# POWER.net
KiCad netlist of a schematic drawn in Altium Designer
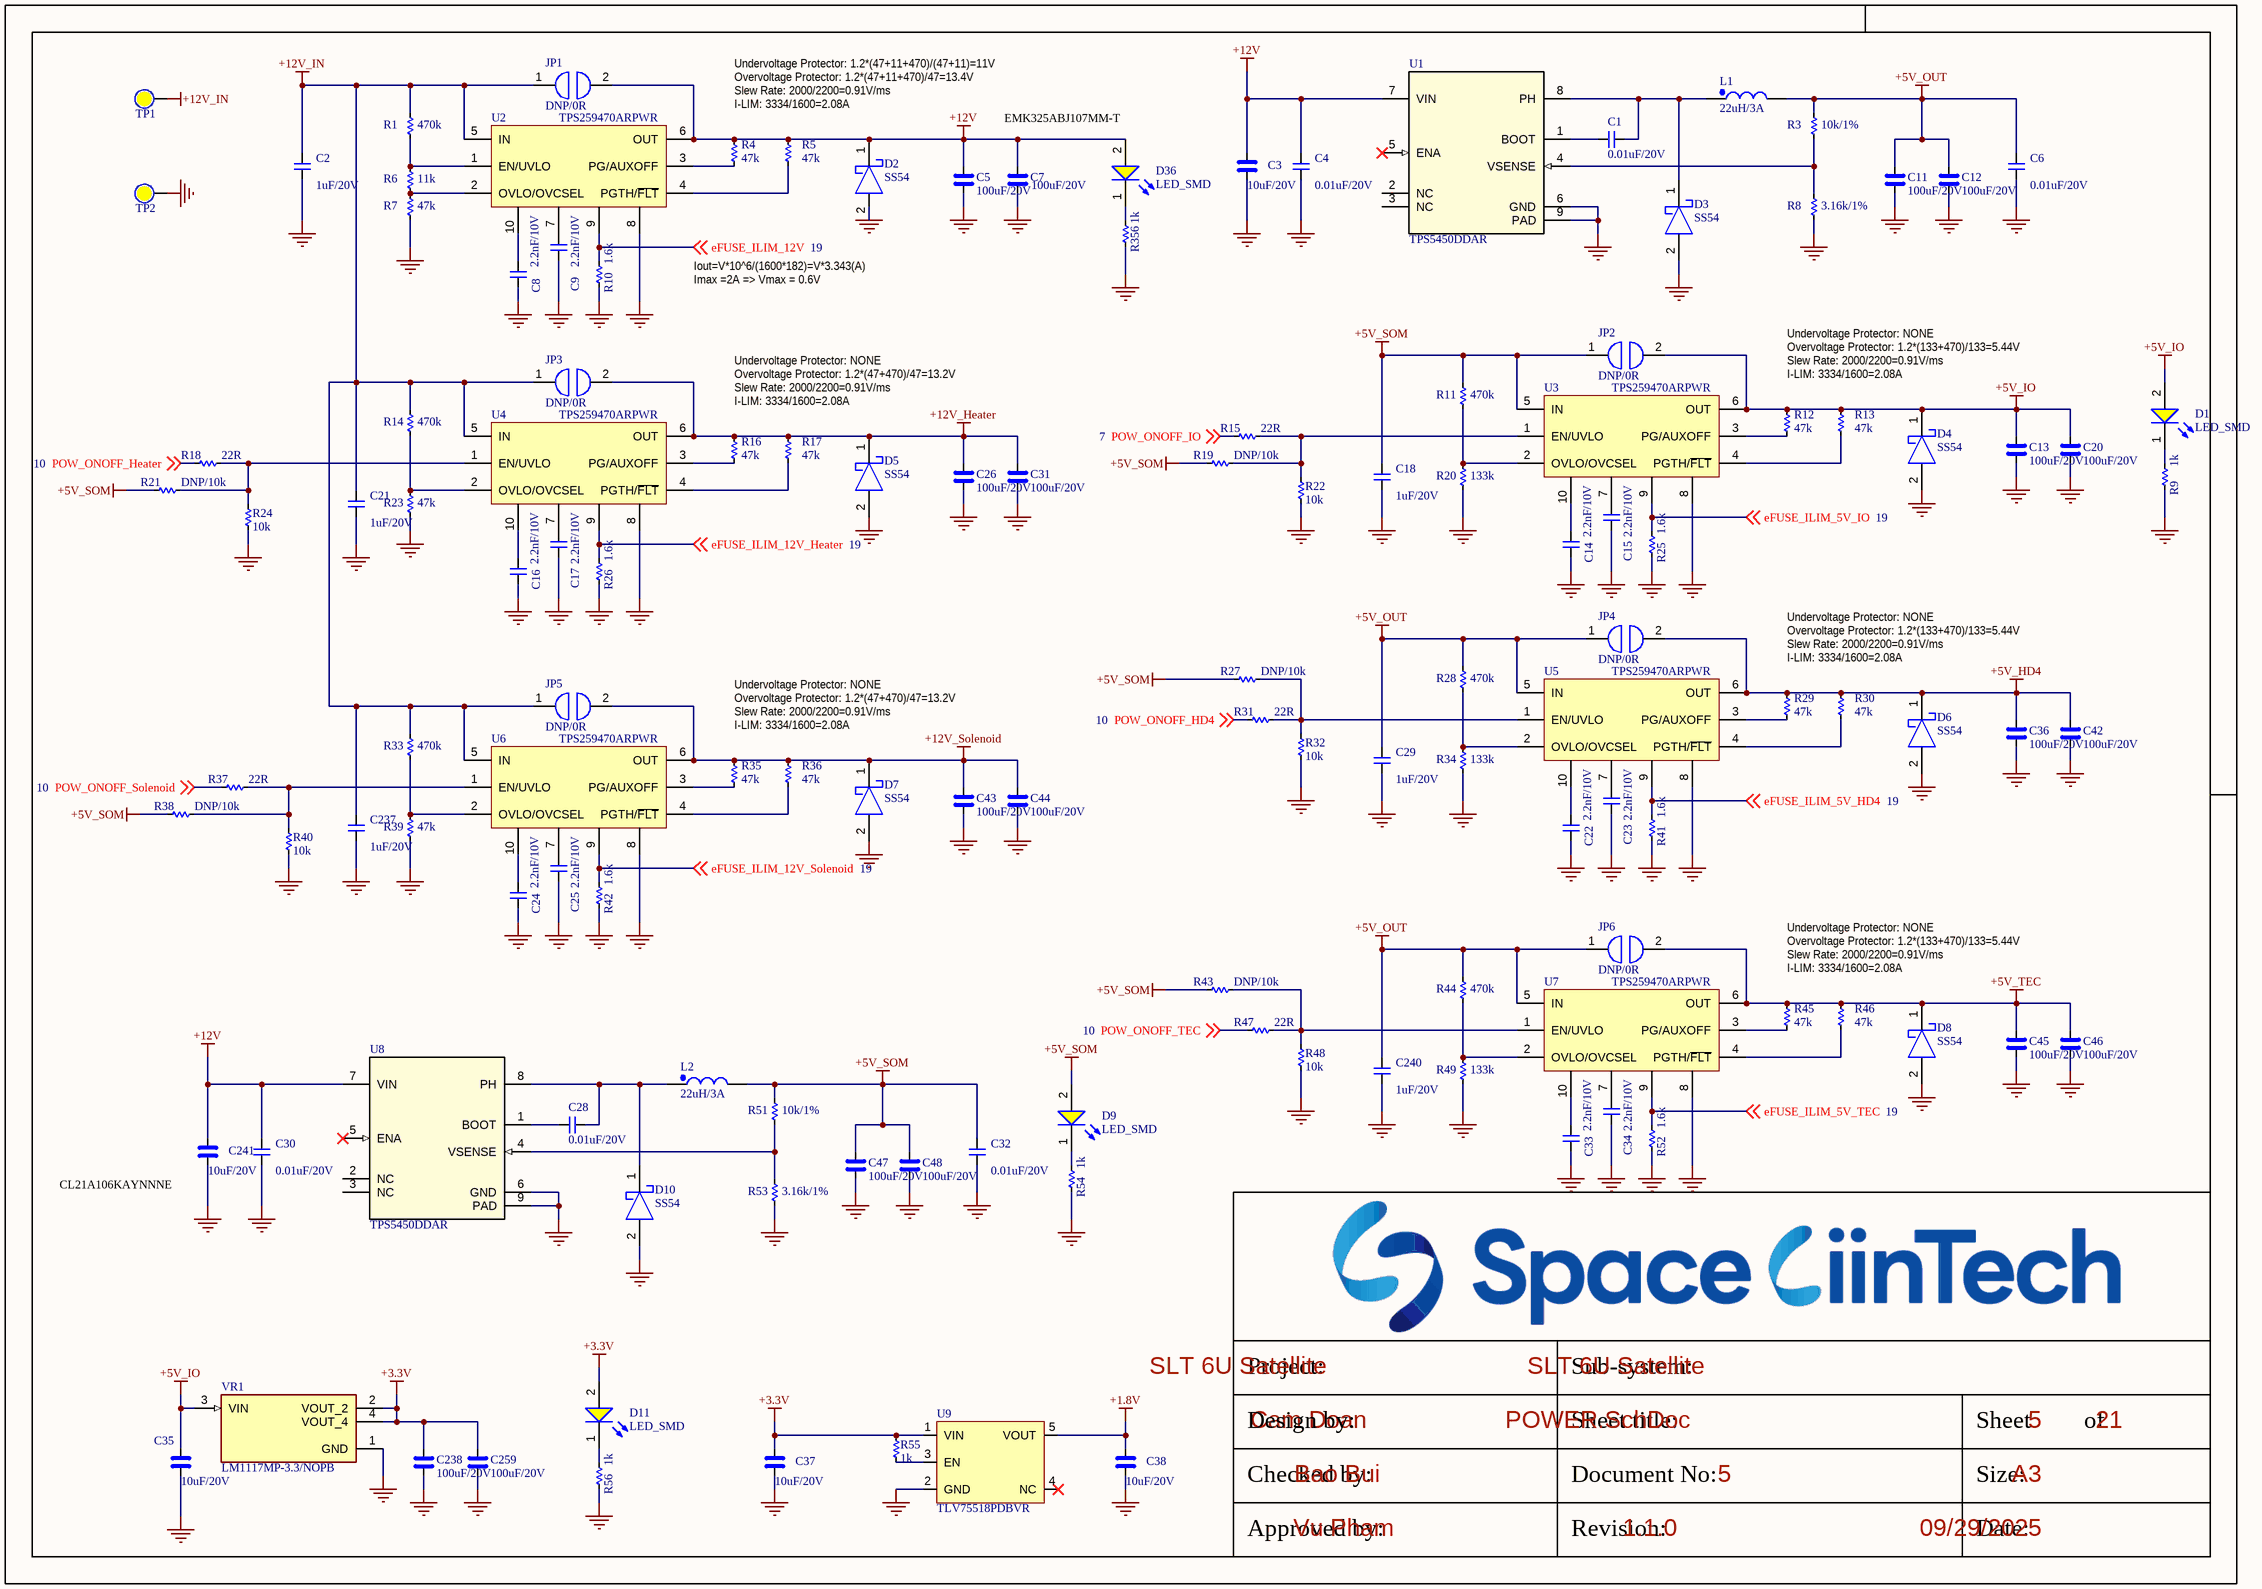
[diagram p0: POWER.SchDoc]

(export (version "E")
  (design (tool "Eeschema 10.0.6"))
  (components
    (comp (ref "C1")
      (value "0.01uF/20V")
      (footprint "CAP_C_1005X60")
      (description "CAP CHIP")
      (libsource (lib "LABLIB") (part "_CAP_C_2"))
    )
    (comp (ref "C2")
      (value "1uF/20V")
      (footprint "CAP_C_1005X60")
      (description "CAP CHIP")
      (libsource (lib "LABLIB") (part "_CAP_C_2"))
    )
    (comp (ref "C3")
      (value "10uF/20V")
      (footprint "CAP_C_2012X110")
      (description "CAP CHIP High Value")
      (libsource (lib "LABLIB") (part "_CAP_C_High_2"))
    )
    (comp (ref "C4")
      (value "0.01uF/20V")
      (footprint "CAP_C_1005X60")
      (description "CAP CHIP")
      (libsource (lib "LABLIB") (part "_CAP_C_2"))
    )
    (comp (ref "C5")
      (value "100uF/20V")
      (footprint "CAP_C_3225X80")
      (description "CAP CHIP High Value")
      (libsource (lib "LABLIB") (part "_CAP_C_High_2"))
    )
    (comp (ref "C6")
      (value "0.01uF/20V")
      (footprint "CAP_C_1005X60")
      (description "CAP CHIP")
      (libsource (lib "LABLIB") (part "_CAP_C_2"))
    )
    (comp (ref "C7")
      (value "100uF/20V")
      (footprint "CAP_C_3225X80")
      (description "CAP CHIP High Value")
      (libsource (lib "LABLIB") (part "_CAP_C_High_2"))
    )
    (comp (ref "C8")
      (value "2.2nF/10V")
      (footprint "CAP_C_1005X60")
      (description "CAP CHIP")
      (libsource (lib "LABLIB") (part "_CAP_C_2"))
    )
    (comp (ref "C9")
      (value "2.2nF/10V")
      (footprint "CAP_C_1005X60")
      (description "CAP CHIP")
      (libsource (lib "LABLIB") (part "_CAP_C_2"))
    )
    (comp (ref "C11")
      (value "100uF/20V")
      (footprint "CAP_C_3225X80")
      (description "CAP CHIP High Value")
      (libsource (lib "LABLIB") (part "_CAP_C_High_2"))
    )
    (comp (ref "C12")
      (value "100uF/20V")
      (footprint "CAP_C_3225X80")
      (description "CAP CHIP High Value")
      (libsource (lib "LABLIB") (part "_CAP_C_High_2"))
    )
    (comp (ref "C13")
      (value "100uF/20V")
      (footprint "CAP_C_3225X80")
      (description "CAP CHIP High Value")
      (libsource (lib "LABLIB") (part "_CAP_C_High_2"))
    )
    (comp (ref "C14")
      (value "2.2nF/10V")
      (footprint "CAP_C_1005X60")
      (description "CAP CHIP")
      (libsource (lib "LABLIB") (part "_CAP_C_2"))
    )
    (comp (ref "C15")
      (value "2.2nF/10V")
      (footprint "CAP_C_1005X60")
      (description "CAP CHIP")
      (libsource (lib "LABLIB") (part "_CAP_C_2"))
    )
    (comp (ref "C16")
      (value "2.2nF/10V")
      (footprint "CAP_C_1005X60")
      (description "CAP CHIP")
      (libsource (lib "LABLIB") (part "_CAP_C_2"))
    )
    (comp (ref "C17")
      (value "2.2nF/10V")
      (footprint "CAP_C_1005X60")
      (description "CAP CHIP")
      (libsource (lib "LABLIB") (part "_CAP_C_2"))
    )
    (comp (ref "C18")
      (value "1uF/20V")
      (footprint "CAP_C_1005X60")
      (description "CAP CHIP")
      (libsource (lib "LABLIB") (part "_CAP_C_2"))
    )
    (comp (ref "C20")
      (value "100uF/20V")
      (footprint "CAP_C_3225X80")
      (description "CAP CHIP High Value")
      (libsource (lib "LABLIB") (part "_CAP_C_High_2"))
    )
    (comp (ref "C21")
      (value "1uF/20V")
      (footprint "CAP_C_1005X60")
      (description "CAP CHIP")
      (libsource (lib "LABLIB") (part "_CAP_C_2"))
    )
    (comp (ref "C22")
      (value "2.2nF/10V")
      (footprint "CAP_C_1005X60")
      (description "CAP CHIP")
      (libsource (lib "LABLIB") (part "_CAP_C_2"))
    )
    (comp (ref "C23")
      (value "2.2nF/10V")
      (footprint "CAP_C_1005X60")
      (description "CAP CHIP")
      (libsource (lib "LABLIB") (part "_CAP_C_2"))
    )
    (comp (ref "C24")
      (value "2.2nF/10V")
      (footprint "CAP_C_1005X60")
      (description "CAP CHIP")
      (libsource (lib "LABLIB") (part "_CAP_C_2"))
    )
    (comp (ref "C25")
      (value "2.2nF/10V")
      (footprint "CAP_C_1005X60")
      (description "CAP CHIP")
      (libsource (lib "LABLIB") (part "_CAP_C_2"))
    )
    (comp (ref "C26")
      (value "100uF/20V")
      (footprint "CAP_C_3225X80")
      (description "CAP CHIP High Value")
      (libsource (lib "LABLIB") (part "_CAP_C_High_2"))
    )
    (comp (ref "C28")
      (value "0.01uF/20V")
      (footprint "CAP_C_1005X60")
      (description "CAP CHIP")
      (libsource (lib "LABLIB") (part "_CAP_C_2"))
    )
    (comp (ref "C29")
      (value "1uF/20V")
      (footprint "CAP_C_1005X60")
      (description "CAP CHIP")
      (libsource (lib "LABLIB") (part "_CAP_C_2"))
    )
    (comp (ref "C30")
      (value "0.01uF/20V")
      (footprint "CAP_C_1005X60")
      (description "CAP CHIP")
      (libsource (lib "LABLIB") (part "_CAP_C_2"))
    )
    (comp (ref "C31")
      (value "100uF/20V")
      (footprint "CAP_C_3225X80")
      (description "CAP CHIP High Value")
      (libsource (lib "LABLIB") (part "_CAP_C_High_2"))
    )
    (comp (ref "C32")
      (value "0.01uF/20V")
      (footprint "CAP_C_1005X60")
      (description "CAP CHIP")
      (libsource (lib "LABLIB") (part "_CAP_C_2"))
    )
    (comp (ref "C33")
      (value "2.2nF/10V")
      (footprint "CAP_C_1005X60")
      (description "CAP CHIP")
      (libsource (lib "LABLIB") (part "_CAP_C_2"))
    )
    (comp (ref "C34")
      (value "2.2nF/10V")
      (footprint "CAP_C_1005X60")
      (description "CAP CHIP")
      (libsource (lib "LABLIB") (part "_CAP_C_2"))
    )
    (comp (ref "C35")
      (value "10uF/20V")
      (footprint "CAP_C_2012X110")
      (description "CAP CHIP High Value")
      (libsource (lib "LABLIB") (part "_CAP_C_High_2"))
    )
    (comp (ref "C36")
      (value "100uF/20V")
      (footprint "CAP_C_3225X80")
      (description "CAP CHIP High Value")
      (libsource (lib "LABLIB") (part "_CAP_C_High_2"))
    )
    (comp (ref "C37")
      (value "10uF/20V")
      (footprint "CAP_C_2012X110")
      (description "CAP CHIP High Value")
      (libsource (lib "LABLIB") (part "_CAP_C_High_2"))
    )
    (comp (ref "C38")
      (value "10uF/20V")
      (footprint "CAP_C_2012X110")
      (description "CAP CHIP High Value")
      (libsource (lib "LABLIB") (part "_CAP_C_High_2"))
    )
    (comp (ref "C42")
      (value "100uF/20V")
      (footprint "CAP_C_3225X80")
      (description "CAP CHIP High Value")
      (libsource (lib "LABLIB") (part "_CAP_C_High_2"))
    )
    (comp (ref "C43")
      (value "100uF/20V")
      (footprint "CAP_C_3225X80")
      (description "CAP CHIP High Value")
      (libsource (lib "LABLIB") (part "_CAP_C_High_2"))
    )
    (comp (ref "C44")
      (value "100uF/20V")
      (footprint "CAP_C_3225X80")
      (description "CAP CHIP High Value")
      (libsource (lib "LABLIB") (part "_CAP_C_High_2"))
    )
    (comp (ref "C45")
      (value "100uF/20V")
      (footprint "CAP_C_3225X80")
      (description "CAP CHIP High Value")
      (libsource (lib "LABLIB") (part "_CAP_C_High_2"))
    )
    (comp (ref "C46")
      (value "100uF/20V")
      (footprint "CAP_C_3225X80")
      (description "CAP CHIP High Value")
      (libsource (lib "LABLIB") (part "_CAP_C_High_2"))
    )
    (comp (ref "C47")
      (value "100uF/20V")
      (footprint "CAP_C_3225X80")
      (description "CAP CHIP High Value")
      (libsource (lib "LABLIB") (part "_CAP_C_High_2"))
    )
    (comp (ref "C48")
      (value "100uF/20V")
      (footprint "CAP_C_3225X80")
      (description "CAP CHIP High Value")
      (libsource (lib "LABLIB") (part "_CAP_C_High_2"))
    )
    (comp (ref "C237")
      (value "1uF/20V")
      (footprint "CAP_C_1005X60")
      (description "CAP CHIP")
      (libsource (lib "LABLIB") (part "_CAP_C_2"))
    )
    (comp (ref "C238")
      (value "100uF/20V")
      (footprint "CAP_C_3225X80")
      (description "CAP CHIP High Value")
      (libsource (lib "LABLIB") (part "_CAP_C_High_2"))
    )
    (comp (ref "C240")
      (value "1uF/20V")
      (footprint "CAP_C_1005X60")
      (description "CAP CHIP")
      (libsource (lib "LABLIB") (part "_CAP_C_2"))
    )
    (comp (ref "C241")
      (value "10uF/20V")
      (footprint "CAP_C_2012X110")
      (description "CAP CHIP High Value")
      (libsource (lib "LABLIB") (part "_CAP_C_High_2"))
    )
    (comp (ref "C259")
      (value "100uF/20V")
      (footprint "CAP_C_3225X80")
      (description "CAP CHIP High Value")
      (libsource (lib "LABLIB") (part "_CAP_C_High_2"))
    )
    (comp (ref "D1") (value "LED_SMD") (footprint "LED_0603") (libsource (lib "LABLIB") (part "LED_SMD")))
    (comp (ref "D2")
      (value "SS54")
      (footprint "DO-214AC_SMA")
      (description "DIODE SCHOTTKY 60V 3A DO214AA")
      (libsource (lib "EXP_HW_V3") (part "SS54"))
    )
    (comp (ref "D3")
      (value "SS54")
      (footprint "DO-214AC_SMA")
      (description "DIODE SCHOTTKY 60V 3A DO214AA")
      (libsource (lib "EXP_HW_V3") (part "SS54"))
    )
    (comp (ref "D4")
      (value "SS54")
      (footprint "DO-214AC_SMA")
      (description "DIODE SCHOTTKY 60V 3A DO214AA")
      (libsource (lib "EXP_HW_V3") (part "SS54"))
    )
    (comp (ref "D5")
      (value "SS54")
      (footprint "DO-214AC_SMA")
      (description "DIODE SCHOTTKY 60V 3A DO214AA")
      (libsource (lib "EXP_HW_V3") (part "SS54"))
    )
    (comp (ref "D6")
      (value "SS54")
      (footprint "DO-214AC_SMA")
      (description "DIODE SCHOTTKY 60V 3A DO214AA")
      (libsource (lib "EXP_HW_V3") (part "SS54"))
    )
    (comp (ref "D7")
      (value "SS54")
      (footprint "DO-214AC_SMA")
      (description "DIODE SCHOTTKY 60V 3A DO214AA")
      (libsource (lib "EXP_HW_V3") (part "SS54"))
    )
    (comp (ref "D8")
      (value "SS54")
      (footprint "DO-214AC_SMA")
      (description "DIODE SCHOTTKY 60V 3A DO214AA")
      (libsource (lib "EXP_HW_V3") (part "SS54"))
    )
    (comp (ref "D9") (value "LED_SMD") (footprint "LED_0603") (libsource (lib "LABLIB") (part "LED_SMD")))
    (comp (ref "D10")
      (value "SS54")
      (footprint "DO-214AC_SMA")
      (description "DIODE SCHOTTKY 60V 3A DO214AA")
      (libsource (lib "EXP_HW_V3") (part "SS54"))
    )
    (comp (ref "D11") (value "LED_SMD") (footprint "LED_0603") (libsource (lib "LABLIB") (part "LED_SMD")))
    (comp (ref "D36") (value "LED_SMD") (footprint "LED_0603") (libsource (lib "LABLIB") (part "LED_SMD")))
    (comp (ref "JP1") (value "DNP/0R") (footprint "RES_C_1608X60") (libsource (lib "EXP_V1") (part "JUMPER")))
    (comp (ref "JP2") (value "DNP/0R") (footprint "RES_C_1608X60") (libsource (lib "EXP_V1") (part "JUMPER")))
    (comp (ref "JP3") (value "DNP/0R") (footprint "RES_C_1608X60") (libsource (lib "EXP_V1") (part "JUMPER")))
    (comp (ref "JP4") (value "DNP/0R") (footprint "RES_C_1608X60") (libsource (lib "EXP_V1") (part "JUMPER")))
    (comp (ref "JP5") (value "DNP/0R") (footprint "RES_C_1608X60") (libsource (lib "EXP_V1") (part "JUMPER")))
    (comp (ref "JP6") (value "DNP/0R") (footprint "RES_C_1608X60") (libsource (lib "EXP_V1") (part "JUMPER")))
    (comp (ref "L1")
      (value "22uH/3A")
      (footprint "IND730660x480")
      (description "SRP7050TA-100M")
      (libsource (lib "LABLIB") (part "_IND"))
    )
    (comp (ref "L2")
      (value "22uH/3A")
      (footprint "IND730660x480")
      (description "SRP7050TA-100M")
      (libsource (lib "LABLIB") (part "_IND"))
    )
    (comp (ref "R1")
      (value "470k")
      (footprint "RES_C_1005X40")
      (description "RES")
      (libsource (lib "LABLIB") (part "_RES_B_2"))
    )
    (comp (ref "R3")
      (value "10k/1%")
      (footprint "RES_C_1005X40")
      (description "RES")
      (libsource (lib "LABLIB") (part "_RES_B_2"))
    )
    (comp (ref "R4")
      (value "47k")
      (footprint "RES_C_1005X40")
      (description "RES")
      (libsource (lib "LABLIB") (part "_RES_B_2"))
    )
    (comp (ref "R5")
      (value "47k")
      (footprint "RES_C_1005X40")
      (description "RES")
      (libsource (lib "LABLIB") (part "_RES_B_2"))
    )
    (comp (ref "R6")
      (value "11k")
      (footprint "RES_C_1005X40")
      (description "RES")
      (libsource (lib "LABLIB") (part "_RES_B_2"))
    )
    (comp (ref "R7")
      (value "47k")
      (footprint "RES_C_1005X40")
      (description "RES")
      (libsource (lib "LABLIB") (part "_RES_B_2"))
    )
    (comp (ref "R8")
      (value "3.16k/1%")
      (footprint "RES_C_1005X40")
      (description "RES")
      (libsource (lib "LABLIB") (part "_RES_B_2"))
    )
    (comp (ref "R9")
      (value "1k")
      (footprint "RES_C_1005X40")
      (description "RES")
      (libsource (lib "LABLIB") (part "_RES_B_2"))
    )
    (comp (ref "R10")
      (value "1.6k")
      (footprint "RES_C_1005X40")
      (description "RES")
      (libsource (lib "LABLIB") (part "_RES_B_2"))
    )
    (comp (ref "R11")
      (value "470k")
      (footprint "RES_C_1005X40")
      (description "RES")
      (libsource (lib "LABLIB") (part "_RES_B_2"))
    )
    (comp (ref "R12")
      (value "47k")
      (footprint "RES_C_1005X40")
      (description "RES")
      (libsource (lib "LABLIB") (part "_RES_B_2"))
    )
    (comp (ref "R13")
      (value "47k")
      (footprint "RES_C_1005X40")
      (description "RES")
      (libsource (lib "LABLIB") (part "_RES_B_2"))
    )
    (comp (ref "R14")
      (value "470k")
      (footprint "RES_C_1005X40")
      (description "RES")
      (libsource (lib "LABLIB") (part "_RES_B_2"))
    )
    (comp (ref "R15")
      (value "22R")
      (footprint "RES_C_1005X40")
      (description "RES")
      (libsource (lib "LABLIB") (part "_RES_B_2"))
    )
    (comp (ref "R16")
      (value "47k")
      (footprint "RES_C_1005X40")
      (description "RES")
      (libsource (lib "LABLIB") (part "_RES_B_2"))
    )
    (comp (ref "R17")
      (value "47k")
      (footprint "RES_C_1005X40")
      (description "RES")
      (libsource (lib "LABLIB") (part "_RES_B_2"))
    )
    (comp (ref "R18")
      (value "22R")
      (footprint "RES_C_1005X40")
      (description "RES")
      (libsource (lib "LABLIB") (part "_RES_B_2"))
    )
    (comp (ref "R19")
      (value "DNP/10k")
      (footprint "RES_C_1005X40")
      (description "RES")
      (libsource (lib "LABLIB") (part "_RES_B_2"))
    )
    (comp (ref "R20")
      (value "133k")
      (footprint "RES_C_1005X40")
      (description "RES")
      (libsource (lib "LABLIB") (part "_RES_B_2"))
    )
    (comp (ref "R21")
      (value "DNP/10k")
      (footprint "RES_C_1005X40")
      (description "RES")
      (libsource (lib "LABLIB") (part "_RES_B_2"))
    )
    (comp (ref "R22")
      (value "10k")
      (footprint "RES_C_1005X40")
      (description "RES")
      (libsource (lib "LABLIB") (part "_RES_B_2"))
    )
    (comp (ref "R23")
      (value "47k")
      (footprint "RES_C_1005X40")
      (description "RES")
      (libsource (lib "LABLIB") (part "_RES_B_2"))
    )
    (comp (ref "R24")
      (value "10k")
      (footprint "RES_C_1005X40")
      (description "RES")
      (libsource (lib "LABLIB") (part "_RES_B_2"))
    )
    (comp (ref "R25")
      (value "1.6k")
      (footprint "RES_C_1005X40")
      (description "RES")
      (libsource (lib "LABLIB") (part "_RES_B_2"))
    )
    (comp (ref "R26")
      (value "1.6k")
      (footprint "RES_C_1005X40")
      (description "RES")
      (libsource (lib "LABLIB") (part "_RES_B_2"))
    )
    (comp (ref "R27")
      (value "DNP/10k")
      (footprint "RES_C_1005X40")
      (description "RES")
      (libsource (lib "LABLIB") (part "_RES_B_2"))
    )
    (comp (ref "R28")
      (value "470k")
      (footprint "RES_C_1005X40")
      (description "RES")
      (libsource (lib "LABLIB") (part "_RES_B_2"))
    )
    (comp (ref "R29")
      (value "47k")
      (footprint "RES_C_1005X40")
      (description "RES")
      (libsource (lib "LABLIB") (part "_RES_B_2"))
    )
    (comp (ref "R30")
      (value "47k")
      (footprint "RES_C_1005X40")
      (description "RES")
      (libsource (lib "LABLIB") (part "_RES_B_2"))
    )
    (comp (ref "R31")
      (value "22R")
      (footprint "RES_C_1005X40")
      (description "RES")
      (libsource (lib "LABLIB") (part "_RES_B_2"))
    )
    (comp (ref "R32")
      (value "10k")
      (footprint "RES_C_1005X40")
      (description "RES")
      (libsource (lib "LABLIB") (part "_RES_B_2"))
    )
    (comp (ref "R33")
      (value "470k")
      (footprint "RES_C_1005X40")
      (description "RES")
      (libsource (lib "LABLIB") (part "_RES_B_2"))
    )
    (comp (ref "R34")
      (value "133k")
      (footprint "RES_C_1005X40")
      (description "RES")
      (libsource (lib "LABLIB") (part "_RES_B_2"))
    )
    (comp (ref "R35")
      (value "47k")
      (footprint "RES_C_1005X40")
      (description "RES")
      (libsource (lib "LABLIB") (part "_RES_B_2"))
    )
    (comp (ref "R36")
      (value "47k")
      (footprint "RES_C_1005X40")
      (description "RES")
      (libsource (lib "LABLIB") (part "_RES_B_2"))
    )
    (comp (ref "R37")
      (value "22R")
      (footprint "RES_C_1005X40")
      (description "RES")
      (libsource (lib "LABLIB") (part "_RES_B_2"))
    )
    (comp (ref "R38")
      (value "DNP/10k")
      (footprint "RES_C_1005X40")
      (description "RES")
      (libsource (lib "LABLIB") (part "_RES_B_2"))
    )
    (comp (ref "R39")
      (value "47k")
      (footprint "RES_C_1005X40")
      (description "RES")
      (libsource (lib "LABLIB") (part "_RES_B_2"))
    )
    (comp (ref "R40")
      (value "10k")
      (footprint "RES_C_1005X40")
      (description "RES")
      (libsource (lib "LABLIB") (part "_RES_B_2"))
    )
    (comp (ref "R41")
      (value "1.6k")
      (footprint "RES_C_1005X40")
      (description "RES")
      (libsource (lib "LABLIB") (part "_RES_B_2"))
    )
    (comp (ref "R42")
      (value "1.6k")
      (footprint "RES_C_1005X40")
      (description "RES")
      (libsource (lib "LABLIB") (part "_RES_B_2"))
    )
    (comp (ref "R43")
      (value "DNP/10k")
      (footprint "RES_C_1005X40")
      (description "RES")
      (libsource (lib "LABLIB") (part "_RES_B_2"))
    )
    (comp (ref "R44")
      (value "470k")
      (footprint "RES_C_1005X40")
      (description "RES")
      (libsource (lib "LABLIB") (part "_RES_B_2"))
    )
    (comp (ref "R45")
      (value "47k")
      (footprint "RES_C_1005X40")
      (description "RES")
      (libsource (lib "LABLIB") (part "_RES_B_2"))
    )
    (comp (ref "R46")
      (value "47k")
      (footprint "RES_C_1005X40")
      (description "RES")
      (libsource (lib "LABLIB") (part "_RES_B_2"))
    )
    (comp (ref "R47")
      (value "22R")
      (footprint "RES_C_1005X40")
      (description "RES")
      (libsource (lib "LABLIB") (part "_RES_B_2"))
    )
    (comp (ref "R48")
      (value "10k")
      (footprint "RES_C_1005X40")
      (description "RES")
      (libsource (lib "LABLIB") (part "_RES_B_2"))
    )
    (comp (ref "R49")
      (value "133k")
      (footprint "RES_C_1005X40")
      (description "RES")
      (libsource (lib "LABLIB") (part "_RES_B_2"))
    )
    (comp (ref "R51")
      (value "10k/1%")
      (footprint "RES_C_1005X40")
      (description "RES")
      (libsource (lib "LABLIB") (part "_RES_B_2"))
    )
    (comp (ref "R52")
      (value "1.6k")
      (footprint "RES_C_1005X40")
      (description "RES")
      (libsource (lib "LABLIB") (part "_RES_B_2"))
    )
    (comp (ref "R53")
      (value "3.16k/1%")
      (footprint "RES_C_1005X40")
      (description "RES")
      (libsource (lib "LABLIB") (part "_RES_B_2"))
    )
    (comp (ref "R54")
      (value "1k")
      (footprint "RES_C_1005X40")
      (description "RES")
      (libsource (lib "LABLIB") (part "_RES_B_2"))
    )
    (comp (ref "R55")
      (value "1k")
      (footprint "RES_C_1005X40")
      (description "RES")
      (libsource (lib "LABLIB") (part "_RES_B_2"))
    )
    (comp (ref "R56")
      (value "1k")
      (footprint "RES_C_1005X40")
      (description "RES")
      (libsource (lib "LABLIB") (part "_RES_B_2"))
    )
    (comp (ref "R356")
      (value "1k")
      (footprint "RES_C_1005X40")
      (description "RES")
      (libsource (lib "LABLIB") (part "_RES_B_2"))
    )
    (comp (ref "TP1")
      (value "~")
      (footprint "Testpoint_TH_D130H80")
      (description "Test Point")
      (libsource (lib "LABLIB") (part "Test Point"))
    )
    (comp (ref "TP2")
      (value "~")
      (footprint "Testpoint_TH_D130H80")
      (description "Test Point")
      (libsource (lib "LABLIB") (part "Test Point"))
    )
    (comp (ref "U1")
      (value "TPS5450DDAR")
      (footprint "DDA0008J")
      (description "No Description Available")
      (libsource (lib "new_component") (part "TPS5430DDAR"))
    )
    (comp (ref "U2")
      (value "TPS259470ARPWR")
      (footprint "VQFN-HR-10")
      (libsource (lib "EXP_HW_V3") (part "TPS259470ARPWR"))
    )
    (comp (ref "U3")
      (value "TPS259470ARPWR")
      (footprint "VQFN-HR-10")
      (libsource (lib "EXP_HW_V3") (part "TPS259470ARPWR"))
    )
    (comp (ref "U4")
      (value "TPS259470ARPWR")
      (footprint "VQFN-HR-10")
      (libsource (lib "EXP_HW_V3") (part "TPS259470ARPWR"))
    )
    (comp (ref "U5")
      (value "TPS259470ARPWR")
      (footprint "VQFN-HR-10")
      (libsource (lib "EXP_HW_V3") (part "TPS259470ARPWR"))
    )
    (comp (ref "U6")
      (value "TPS259470ARPWR")
      (footprint "VQFN-HR-10")
      (libsource (lib "EXP_HW_V3") (part "TPS259470ARPWR"))
    )
    (comp (ref "U7")
      (value "TPS259470ARPWR")
      (footprint "VQFN-HR-10")
      (libsource (lib "EXP_HW_V3") (part "TPS259470ARPWR"))
    )
    (comp (ref "U8")
      (value "TPS5450DDAR")
      (footprint "DDA0008J")
      (description "No Description Available")
      (libsource (lib "new_component") (part "TPS5430DDAR"))
    )
    (comp (ref "U9")
      (value "TLV75518PDBVR")
      (footprint "SOT25")
      (libsource (lib "CAMERA_SchLib") (part "IC_POWER_AP7347DQ"))
    )
    (comp (ref "VR1")
      (value "LM1117MP-3.3/NOPB")
      (footprint "VREG_LM1117MP-3.3/NOPB")
      (description "800-mA 15-V linear voltage regulator")
      (fields (field (name "MF") "Texas Instruments"))
      (libsource (lib "new_component") (part "LM1117MP-3.3/NOPB"))
    )
  )
  (nets
    (net (code "1") (name "+1.8V") (class "Default")
      (node (ref "C38") (pin "1") (pinfunction "1_1") (pintype "passive"))
      (node (ref "U9") (pin "5") (pinfunction "VOUT_5") (pintype "passive"))
    )
    (net (code "2") (name "+3.3V") (class "Default")
      (node (ref "C238") (pin "2") (pinfunction "2_2") (pintype "passive"))
      (node (ref "C259") (pin "2") (pinfunction "2_2") (pintype "passive"))
      (node (ref "C37") (pin "1") (pinfunction "1_1") (pintype "passive"))
      (node (ref "D11") (pin "2") (pinfunction "A_2") (pintype "passive"))
      (node (ref "R55") (pin "2") (pinfunction "2_2") (pintype "passive"))
      (node (ref "U9") (pin "1") (pinfunction "VIN_1") (pintype "passive"))
      (node (ref "VR1") (pin "2") (pinfunction "VOUT_2_2") (pintype "power_in"))
      (node (ref "VR1") (pin "4") (pinfunction "VOUT_4_4") (pintype "power_in"))
    )
    (net (code "3") (name "+5V_HD4") (class "Default")
      (node (ref "C36") (pin "2") (pinfunction "2_2") (pintype "passive"))
      (node (ref "C42") (pin "2") (pinfunction "2_2") (pintype "passive"))
      (node (ref "D6") (pin "1") (pinfunction "1_1") (pintype "passive"))
      (node (ref "JP4") (pin "2") (pinfunction "2_2") (pintype "passive"))
      (node (ref "R29") (pin "2") (pinfunction "2_2") (pintype "passive"))
      (node (ref "R30") (pin "2") (pinfunction "2_2") (pintype "passive"))
      (node (ref "U5") (pin "6") (pinfunction "OUT_6") (pintype "passive"))
    )
    (net (code "4") (name "+5V_IO") (class "Default")
      (node (ref "C13") (pin "2") (pinfunction "2_2") (pintype "passive"))
      (node (ref "C20") (pin "2") (pinfunction "2_2") (pintype "passive"))
      (node (ref "C35") (pin "1") (pinfunction "1_1") (pintype "passive"))
      (node (ref "D1") (pin "2") (pinfunction "A_2") (pintype "passive"))
      (node (ref "D4") (pin "1") (pinfunction "1_1") (pintype "passive"))
      (node (ref "JP2") (pin "2") (pinfunction "2_2") (pintype "passive"))
      (node (ref "R12") (pin "2") (pinfunction "2_2") (pintype "passive"))
      (node (ref "R13") (pin "2") (pinfunction "2_2") (pintype "passive"))
      (node (ref "U3") (pin "6") (pinfunction "OUT_6") (pintype "passive"))
      (node (ref "VR1") (pin "3") (pinfunction "VIN_3") (pintype "input"))
    )
    (net (code "5") (name "+5V_OUT") (class "Default")
      (node (ref "C11") (pin "2") (pinfunction "2_2") (pintype "passive"))
      (node (ref "C12") (pin "2") (pinfunction "2_2") (pintype "passive"))
      (node (ref "C240") (pin "2") (pinfunction "2_2") (pintype "passive"))
      (node (ref "C29") (pin "2") (pinfunction "2_2") (pintype "passive"))
      (node (ref "C6") (pin "2") (pinfunction "2_2") (pintype "passive"))
      (node (ref "JP4") (pin "1") (pinfunction "1_1") (pintype "passive"))
      (node (ref "JP6") (pin "1") (pinfunction "1_1") (pintype "passive"))
      (node (ref "L1") (pin "2") (pinfunction "2_2") (pintype "passive"))
      (node (ref "R28") (pin "2") (pinfunction "2_2") (pintype "passive"))
      (node (ref "R3") (pin "2") (pinfunction "2_2") (pintype "passive"))
      (node (ref "R44") (pin "2") (pinfunction "2_2") (pintype "passive"))
      (node (ref "U5") (pin "5") (pinfunction "IN_5") (pintype "passive"))
      (node (ref "U7") (pin "5") (pinfunction "IN_5") (pintype "passive"))
    )
    (net (code "6") (name "+5V_SOM") (class "Default")
      (node (ref "C18") (pin "2") (pinfunction "2_2") (pintype "passive"))
      (node (ref "C32") (pin "2") (pinfunction "2_2") (pintype "passive"))
      (node (ref "C47") (pin "2") (pinfunction "2_2") (pintype "passive"))
      (node (ref "C48") (pin "2") (pinfunction "2_2") (pintype "passive"))
      (node (ref "D9") (pin "2") (pinfunction "A_2") (pintype "passive"))
      (node (ref "JP2") (pin "1") (pinfunction "1_1") (pintype "passive"))
      (node (ref "L2") (pin "2") (pinfunction "2_2") (pintype "passive"))
      (node (ref "R11") (pin "2") (pinfunction "2_2") (pintype "passive"))
      (node (ref "R19") (pin "2") (pinfunction "2_2") (pintype "passive"))
      (node (ref "R21") (pin "2") (pinfunction "2_2") (pintype "passive"))
      (node (ref "R27") (pin "2") (pinfunction "2_2") (pintype "passive"))
      (node (ref "R38") (pin "2") (pinfunction "2_2") (pintype "passive"))
      (node (ref "R43") (pin "2") (pinfunction "2_2") (pintype "passive"))
      (node (ref "R51") (pin "2") (pinfunction "2_2") (pintype "passive"))
      (node (ref "U3") (pin "5") (pinfunction "IN_5") (pintype "passive"))
    )
    (net (code "7") (name "+5V_TEC") (class "Default")
      (node (ref "C45") (pin "2") (pinfunction "2_2") (pintype "passive"))
      (node (ref "C46") (pin "2") (pinfunction "2_2") (pintype "passive"))
      (node (ref "D8") (pin "1") (pinfunction "1_1") (pintype "passive"))
      (node (ref "JP6") (pin "2") (pinfunction "2_2") (pintype "passive"))
      (node (ref "R45") (pin "2") (pinfunction "2_2") (pintype "passive"))
      (node (ref "R46") (pin "2") (pinfunction "2_2") (pintype "passive"))
      (node (ref "U7") (pin "6") (pinfunction "OUT_6") (pintype "passive"))
    )
    (net (code "8") (name "+12V") (class "Default")
      (node (ref "C241") (pin "1") (pinfunction "1_1") (pintype "passive"))
      (node (ref "C3") (pin "1") (pinfunction "1_1") (pintype "passive"))
      (node (ref "C30") (pin "2") (pinfunction "2_2") (pintype "passive"))
      (node (ref "C4") (pin "2") (pinfunction "2_2") (pintype "passive"))
      (node (ref "C5") (pin "2") (pinfunction "2_2") (pintype "passive"))
      (node (ref "C7") (pin "2") (pinfunction "2_2") (pintype "passive"))
      (node (ref "D2") (pin "1") (pinfunction "1_1") (pintype "passive"))
      (node (ref "D36") (pin "2") (pinfunction "A_2") (pintype "passive"))
      (node (ref "JP1") (pin "2") (pinfunction "2_2") (pintype "passive"))
      (node (ref "R4") (pin "2") (pinfunction "2_2") (pintype "passive"))
      (node (ref "R5") (pin "2") (pinfunction "2_2") (pintype "passive"))
      (node (ref "U1") (pin "7") (pinfunction "VIN_7") (pintype "power_in"))
      (node (ref "U2") (pin "6") (pinfunction "OUT_6") (pintype "passive"))
      (node (ref "U8") (pin "7") (pinfunction "VIN_7") (pintype "power_in"))
    )
    (net (code "9") (name "+12V_Heater") (class "Default")
      (node (ref "C26") (pin "2") (pinfunction "2_2") (pintype "passive"))
      (node (ref "C31") (pin "2") (pinfunction "2_2") (pintype "passive"))
      (node (ref "D5") (pin "1") (pinfunction "1_1") (pintype "passive"))
      (node (ref "JP3") (pin "2") (pinfunction "2_2") (pintype "passive"))
      (node (ref "R16") (pin "2") (pinfunction "2_2") (pintype "passive"))
      (node (ref "R17") (pin "2") (pinfunction "2_2") (pintype "passive"))
      (node (ref "U4") (pin "6") (pinfunction "OUT_6") (pintype "passive"))
    )
    (net (code "10") (name "+12V_IN") (class "Default")
      (node (ref "C2") (pin "2") (pinfunction "2_2") (pintype "passive"))
      (node (ref "C21") (pin "2") (pinfunction "2_2") (pintype "passive"))
      (node (ref "C237") (pin "2") (pinfunction "2_2") (pintype "passive"))
      (node (ref "JP1") (pin "1") (pinfunction "1_1") (pintype "passive"))
      (node (ref "JP3") (pin "1") (pinfunction "1_1") (pintype "passive"))
      (node (ref "JP5") (pin "1") (pinfunction "1_1") (pintype "passive"))
      (node (ref "R1") (pin "2") (pinfunction "2_2") (pintype "passive"))
      (node (ref "R14") (pin "2") (pinfunction "2_2") (pintype "passive"))
      (node (ref "R33") (pin "2") (pinfunction "2_2") (pintype "passive"))
      (node (ref "TP1") (pin "0") (pinfunction "0_0") (pintype "passive"))
      (node (ref "U2") (pin "5") (pinfunction "IN_5") (pintype "passive"))
      (node (ref "U4") (pin "5") (pinfunction "IN_5") (pintype "passive"))
      (node (ref "U6") (pin "5") (pinfunction "IN_5") (pintype "passive"))
    )
    (net (code "11") (name "+12V_Solenoid") (class "Default")
      (node (ref "C43") (pin "2") (pinfunction "2_2") (pintype "passive"))
      (node (ref "C44") (pin "2") (pinfunction "2_2") (pintype "passive"))
      (node (ref "D7") (pin "1") (pinfunction "1_1") (pintype "passive"))
      (node (ref "JP5") (pin "2") (pinfunction "2_2") (pintype "passive"))
      (node (ref "R35") (pin "2") (pinfunction "2_2") (pintype "passive"))
      (node (ref "R36") (pin "2") (pinfunction "2_2") (pintype "passive"))
      (node (ref "U6") (pin "6") (pinfunction "OUT_6") (pintype "passive"))
    )
    (net (code "12") (name "GND") (class "Default")
      (node (ref "C11") (pin "1") (pinfunction "1_1") (pintype "passive"))
      (node (ref "C12") (pin "1") (pinfunction "1_1") (pintype "passive"))
      (node (ref "C13") (pin "1") (pinfunction "1_1") (pintype "passive"))
      (node (ref "C14") (pin "1") (pinfunction "1_1") (pintype "passive"))
      (node (ref "C15") (pin "1") (pinfunction "1_1") (pintype "passive"))
      (node (ref "C16") (pin "1") (pinfunction "1_1") (pintype "passive"))
      (node (ref "C17") (pin "1") (pinfunction "1_1") (pintype "passive"))
      (node (ref "C18") (pin "1") (pinfunction "1_1") (pintype "passive"))
      (node (ref "C2") (pin "1") (pinfunction "1_1") (pintype "passive"))
      (node (ref "C20") (pin "1") (pinfunction "1_1") (pintype "passive"))
      (node (ref "C21") (pin "1") (pinfunction "1_1") (pintype "passive"))
      (node (ref "C22") (pin "1") (pinfunction "1_1") (pintype "passive"))
      (node (ref "C23") (pin "1") (pinfunction "1_1") (pintype "passive"))
      (node (ref "C237") (pin "1") (pinfunction "1_1") (pintype "passive"))
      (node (ref "C238") (pin "1") (pinfunction "1_1") (pintype "passive"))
      (node (ref "C24") (pin "1") (pinfunction "1_1") (pintype "passive"))
      (node (ref "C240") (pin "1") (pinfunction "1_1") (pintype "passive"))
      (node (ref "C241") (pin "2") (pinfunction "2_2") (pintype "passive"))
      (node (ref "C25") (pin "1") (pinfunction "1_1") (pintype "passive"))
      (node (ref "C259") (pin "1") (pinfunction "1_1") (pintype "passive"))
      (node (ref "C26") (pin "1") (pinfunction "1_1") (pintype "passive"))
      (node (ref "C29") (pin "1") (pinfunction "1_1") (pintype "passive"))
      (node (ref "C3") (pin "2") (pinfunction "2_2") (pintype "passive"))
      (node (ref "C30") (pin "1") (pinfunction "1_1") (pintype "passive"))
      (node (ref "C31") (pin "1") (pinfunction "1_1") (pintype "passive"))
      (node (ref "C32") (pin "1") (pinfunction "1_1") (pintype "passive"))
      (node (ref "C33") (pin "1") (pinfunction "1_1") (pintype "passive"))
      (node (ref "C34") (pin "1") (pinfunction "1_1") (pintype "passive"))
      (node (ref "C35") (pin "2") (pinfunction "2_2") (pintype "passive"))
      (node (ref "C36") (pin "1") (pinfunction "1_1") (pintype "passive"))
      (node (ref "C37") (pin "2") (pinfunction "2_2") (pintype "passive"))
      (node (ref "C38") (pin "2") (pinfunction "2_2") (pintype "passive"))
      (node (ref "C4") (pin "1") (pinfunction "1_1") (pintype "passive"))
      (node (ref "C42") (pin "1") (pinfunction "1_1") (pintype "passive"))
      (node (ref "C43") (pin "1") (pinfunction "1_1") (pintype "passive"))
      (node (ref "C44") (pin "1") (pinfunction "1_1") (pintype "passive"))
      (node (ref "C45") (pin "1") (pinfunction "1_1") (pintype "passive"))
      (node (ref "C46") (pin "1") (pinfunction "1_1") (pintype "passive"))
      (node (ref "C47") (pin "1") (pinfunction "1_1") (pintype "passive"))
      (node (ref "C48") (pin "1") (pinfunction "1_1") (pintype "passive"))
      (node (ref "C5") (pin "1") (pinfunction "1_1") (pintype "passive"))
      (node (ref "C6") (pin "1") (pinfunction "1_1") (pintype "passive"))
      (node (ref "C7") (pin "1") (pinfunction "1_1") (pintype "passive"))
      (node (ref "C8") (pin "1") (pinfunction "1_1") (pintype "passive"))
      (node (ref "C9") (pin "1") (pinfunction "1_1") (pintype "passive"))
      (node (ref "D10") (pin "2") (pinfunction "2_2") (pintype "passive"))
      (node (ref "D2") (pin "2") (pinfunction "2_2") (pintype "passive"))
      (node (ref "D3") (pin "2") (pinfunction "2_2") (pintype "passive"))
      (node (ref "D4") (pin "2") (pinfunction "2_2") (pintype "passive"))
      (node (ref "D5") (pin "2") (pinfunction "2_2") (pintype "passive"))
      (node (ref "D6") (pin "2") (pinfunction "2_2") (pintype "passive"))
      (node (ref "D7") (pin "2") (pinfunction "2_2") (pintype "passive"))
      (node (ref "D8") (pin "2") (pinfunction "2_2") (pintype "passive"))
      (node (ref "R10") (pin "1") (pinfunction "1_1") (pintype "passive"))
      (node (ref "R20") (pin "1") (pinfunction "1_1") (pintype "passive"))
      (node (ref "R22") (pin "2") (pinfunction "2_2") (pintype "passive"))
      (node (ref "R23") (pin "1") (pinfunction "1_1") (pintype "passive"))
      (node (ref "R24") (pin "2") (pinfunction "2_2") (pintype "passive"))
      (node (ref "R25") (pin "1") (pinfunction "1_1") (pintype "passive"))
      (node (ref "R26") (pin "1") (pinfunction "1_1") (pintype "passive"))
      (node (ref "R32") (pin "2") (pinfunction "2_2") (pintype "passive"))
      (node (ref "R34") (pin "1") (pinfunction "1_1") (pintype "passive"))
      (node (ref "R356") (pin "1") (pinfunction "1_1") (pintype "passive"))
      (node (ref "R39") (pin "1") (pinfunction "1_1") (pintype "passive"))
      (node (ref "R40") (pin "2") (pinfunction "2_2") (pintype "passive"))
      (node (ref "R41") (pin "1") (pinfunction "1_1") (pintype "passive"))
      (node (ref "R42") (pin "1") (pinfunction "1_1") (pintype "passive"))
      (node (ref "R48") (pin "2") (pinfunction "2_2") (pintype "passive"))
      (node (ref "R49") (pin "1") (pinfunction "1_1") (pintype "passive"))
      (node (ref "R52") (pin "1") (pinfunction "1_1") (pintype "passive"))
      (node (ref "R53") (pin "1") (pinfunction "1_1") (pintype "passive"))
      (node (ref "R54") (pin "1") (pinfunction "1_1") (pintype "passive"))
      (node (ref "R56") (pin "1") (pinfunction "1_1") (pintype "passive"))
      (node (ref "R7") (pin "1") (pinfunction "1_1") (pintype "passive"))
      (node (ref "R8") (pin "1") (pinfunction "1_1") (pintype "passive"))
      (node (ref "R9") (pin "1") (pinfunction "1_1") (pintype "passive"))
      (node (ref "TP2") (pin "0") (pinfunction "0_0") (pintype "passive"))
      (node (ref "U1") (pin "6") (pinfunction "GND_6") (pintype "power_in"))
      (node (ref "U1") (pin "9") (pinfunction "PAD_9") (pintype "power_in"))
      (node (ref "U2") (pin "8") (pinfunction "8_8") (pintype "passive"))
      (node (ref "U3") (pin "8") (pinfunction "8_8") (pintype "passive"))
      (node (ref "U4") (pin "8") (pinfunction "8_8") (pintype "passive"))
      (node (ref "U5") (pin "8") (pinfunction "8_8") (pintype "passive"))
      (node (ref "U6") (pin "8") (pinfunction "8_8") (pintype "passive"))
      (node (ref "U7") (pin "8") (pinfunction "8_8") (pintype "passive"))
      (node (ref "U8") (pin "6") (pinfunction "GND_6") (pintype "power_in"))
      (node (ref "U8") (pin "9") (pinfunction "PAD_9") (pintype "power_in"))
      (node (ref "U9") (pin "2") (pinfunction "GND_2") (pintype "passive"))
      (node (ref "VR1") (pin "1") (pinfunction "GND_1") (pintype "power_in"))
    )
    (net (code "13") (name "Net-(C8-Pad2)") (class "Default")
      (node (ref "C8") (pin "2") (pinfunction "2_2") (pintype "passive"))
      (node (ref "U2") (pin "10") (pinfunction "10_10") (pintype "passive"))
    )
    (net (code "14") (name "Net-(C9-Pad2)") (class "Default")
      (node (ref "C9") (pin "2") (pinfunction "2_2") (pintype "passive"))
      (node (ref "U2") (pin "7") (pinfunction "7_7") (pintype "passive"))
    )
    (net (code "15") (name "Net-(C14-Pad2)") (class "Default")
      (node (ref "C14") (pin "2") (pinfunction "2_2") (pintype "passive"))
      (node (ref "U3") (pin "10") (pinfunction "10_10") (pintype "passive"))
    )
    (net (code "16") (name "Net-(C15-Pad2)") (class "Default")
      (node (ref "C15") (pin "2") (pinfunction "2_2") (pintype "passive"))
      (node (ref "U3") (pin "7") (pinfunction "7_7") (pintype "passive"))
    )
    (net (code "17") (name "Net-(C16-Pad2)") (class "Default")
      (node (ref "C16") (pin "2") (pinfunction "2_2") (pintype "passive"))
      (node (ref "U4") (pin "10") (pinfunction "10_10") (pintype "passive"))
    )
    (net (code "18") (name "Net-(C17-Pad2)") (class "Default")
      (node (ref "C17") (pin "2") (pinfunction "2_2") (pintype "passive"))
      (node (ref "U4") (pin "7") (pinfunction "7_7") (pintype "passive"))
    )
    (net (code "19") (name "Net-(C22-Pad2)") (class "Default")
      (node (ref "C22") (pin "2") (pinfunction "2_2") (pintype "passive"))
      (node (ref "U5") (pin "10") (pinfunction "10_10") (pintype "passive"))
    )
    (net (code "20") (name "Net-(C23-Pad2)") (class "Default")
      (node (ref "C23") (pin "2") (pinfunction "2_2") (pintype "passive"))
      (node (ref "U5") (pin "7") (pinfunction "7_7") (pintype "passive"))
    )
    (net (code "21") (name "Net-(C24-Pad2)") (class "Default")
      (node (ref "C24") (pin "2") (pinfunction "2_2") (pintype "passive"))
      (node (ref "U6") (pin "10") (pinfunction "10_10") (pintype "passive"))
    )
    (net (code "22") (name "Net-(C25-Pad2)") (class "Default")
      (node (ref "C25") (pin "2") (pinfunction "2_2") (pintype "passive"))
      (node (ref "U6") (pin "7") (pinfunction "7_7") (pintype "passive"))
    )
    (net (code "23") (name "Net-(C33-Pad2)") (class "Default")
      (node (ref "C33") (pin "2") (pinfunction "2_2") (pintype "passive"))
      (node (ref "U7") (pin "10") (pinfunction "10_10") (pintype "passive"))
    )
    (net (code "24") (name "Net-(C34-Pad2)") (class "Default")
      (node (ref "C34") (pin "2") (pinfunction "2_2") (pintype "passive"))
      (node (ref "U7") (pin "7") (pinfunction "7_7") (pintype "passive"))
    )
    (net (code "25") (name "Net-(D1-K)") (class "Default")
      (node (ref "D1") (pin "1") (pinfunction "K_1") (pintype "passive"))
      (node (ref "R9") (pin "2") (pinfunction "2_2") (pintype "passive"))
    )
    (net (code "26") (name "Net-(D9-K)") (class "Default")
      (node (ref "D9") (pin "1") (pinfunction "K_1") (pintype "passive"))
      (node (ref "R54") (pin "2") (pinfunction "2_2") (pintype "passive"))
    )
    (net (code "27") (name "Net-(D11-K)") (class "Default")
      (node (ref "D11") (pin "1") (pinfunction "K_1") (pintype "passive"))
      (node (ref "R56") (pin "2") (pinfunction "2_2") (pintype "passive"))
    )
    (net (code "28") (name "Net-(D36-K)") (class "Default")
      (node (ref "D36") (pin "1") (pinfunction "K_1") (pintype "passive"))
      (node (ref "R356") (pin "2") (pinfunction "2_2") (pintype "passive"))
    )
    (net (code "29") (name "Net-(U1-BOOT)") (class "Default")
      (node (ref "C1") (pin "2") (pinfunction "2_2") (pintype "passive"))
      (node (ref "U1") (pin "1") (pinfunction "BOOT_1") (pintype "power_in"))
    )
    (net (code "30") (name "Net-(U1-PH)") (class "Default")
      (node (ref "C1") (pin "1") (pinfunction "1_1") (pintype "passive"))
      (node (ref "D3") (pin "1") (pinfunction "1_1") (pintype "passive"))
      (node (ref "L1") (pin "1") (pinfunction "1_1") (pintype "passive"))
      (node (ref "U1") (pin "8") (pinfunction "PH_8") (pintype "power_in"))
    )
    (net (code "31") (name "Net-(U1-VSENSE)") (class "Default")
      (node (ref "R3") (pin "1") (pinfunction "1_1") (pintype "passive"))
      (node (ref "R8") (pin "2") (pinfunction "2_2") (pintype "passive"))
      (node (ref "U1") (pin "4") (pinfunction "VSENSE_4") (pintype "input"))
    )
    (net (code "32") (name "Net-(U2-EN{slash}UVLO)") (class "Default")
      (node (ref "R1") (pin "1") (pinfunction "1_1") (pintype "passive"))
      (node (ref "R6") (pin "2") (pinfunction "2_2") (pintype "passive"))
      (node (ref "U2") (pin "1") (pinfunction "EN/UVLO_1") (pintype "passive"))
    )
    (net (code "33") (name "Net-(U2-OVLO{slash}OVCSEL)") (class "Default")
      (node (ref "R6") (pin "1") (pinfunction "1_1") (pintype "passive"))
      (node (ref "R7") (pin "2") (pinfunction "2_2") (pintype "passive"))
      (node (ref "U2") (pin "2") (pinfunction "OVLO/OVCSEL_2") (pintype "passive"))
    )
    (net (code "34") (name "Net-(U2-PGTH{slash}~{FLT})") (class "Default")
      (node (ref "R5") (pin "1") (pinfunction "1_1") (pintype "passive"))
      (node (ref "U2") (pin "4") (pinfunction "PGTH/~{FLT}_4") (pintype "passive"))
    )
    (net (code "35") (name "Net-(U2-PG{slash}AUXOFF)") (class "Default")
      (node (ref "R4") (pin "1") (pinfunction "1_1") (pintype "passive"))
      (node (ref "U2") (pin "3") (pinfunction "PG/AUXOFF_3") (pintype "passive"))
    )
    (net (code "36") (name "Net-(U3-EN{slash}UVLO)") (class "Default")
      (node (ref "R15") (pin "1") (pinfunction "1_1") (pintype "passive"))
      (node (ref "R19") (pin "1") (pinfunction "1_1") (pintype "passive"))
      (node (ref "R22") (pin "1") (pinfunction "1_1") (pintype "passive"))
      (node (ref "U3") (pin "1") (pinfunction "EN/UVLO_1") (pintype "passive"))
    )
    (net (code "37") (name "Net-(U3-OVLO{slash}OVCSEL)") (class "Default")
      (node (ref "R11") (pin "1") (pinfunction "1_1") (pintype "passive"))
      (node (ref "R20") (pin "2") (pinfunction "2_2") (pintype "passive"))
      (node (ref "U3") (pin "2") (pinfunction "OVLO/OVCSEL_2") (pintype "passive"))
    )
    (net (code "38") (name "Net-(U3-PGTH{slash}~{FLT})") (class "Default")
      (node (ref "R13") (pin "1") (pinfunction "1_1") (pintype "passive"))
      (node (ref "U3") (pin "4") (pinfunction "PGTH/~{FLT}_4") (pintype "passive"))
    )
    (net (code "39") (name "Net-(U3-PG{slash}AUXOFF)") (class "Default")
      (node (ref "R12") (pin "1") (pinfunction "1_1") (pintype "passive"))
      (node (ref "U3") (pin "3") (pinfunction "PG/AUXOFF_3") (pintype "passive"))
    )
    (net (code "40") (name "Net-(U4-EN{slash}UVLO)") (class "Default")
      (node (ref "R18") (pin "1") (pinfunction "1_1") (pintype "passive"))
      (node (ref "R21") (pin "1") (pinfunction "1_1") (pintype "passive"))
      (node (ref "R24") (pin "1") (pinfunction "1_1") (pintype "passive"))
      (node (ref "U4") (pin "1") (pinfunction "EN/UVLO_1") (pintype "passive"))
    )
    (net (code "41") (name "Net-(U4-OVLO{slash}OVCSEL)") (class "Default")
      (node (ref "R14") (pin "1") (pinfunction "1_1") (pintype "passive"))
      (node (ref "R23") (pin "2") (pinfunction "2_2") (pintype "passive"))
      (node (ref "U4") (pin "2") (pinfunction "OVLO/OVCSEL_2") (pintype "passive"))
    )
    (net (code "42") (name "Net-(U4-PGTH{slash}~{FLT})") (class "Default")
      (node (ref "R17") (pin "1") (pinfunction "1_1") (pintype "passive"))
      (node (ref "U4") (pin "4") (pinfunction "PGTH/~{FLT}_4") (pintype "passive"))
    )
    (net (code "43") (name "Net-(U4-PG{slash}AUXOFF)") (class "Default")
      (node (ref "R16") (pin "1") (pinfunction "1_1") (pintype "passive"))
      (node (ref "U4") (pin "3") (pinfunction "PG/AUXOFF_3") (pintype "passive"))
    )
    (net (code "44") (name "Net-(U5-EN{slash}UVLO)") (class "Default")
      (node (ref "R27") (pin "1") (pinfunction "1_1") (pintype "passive"))
      (node (ref "R31") (pin "1") (pinfunction "1_1") (pintype "passive"))
      (node (ref "R32") (pin "1") (pinfunction "1_1") (pintype "passive"))
      (node (ref "U5") (pin "1") (pinfunction "EN/UVLO_1") (pintype "passive"))
    )
    (net (code "45") (name "Net-(U5-OVLO{slash}OVCSEL)") (class "Default")
      (node (ref "R28") (pin "1") (pinfunction "1_1") (pintype "passive"))
      (node (ref "R34") (pin "2") (pinfunction "2_2") (pintype "passive"))
      (node (ref "U5") (pin "2") (pinfunction "OVLO/OVCSEL_2") (pintype "passive"))
    )
    (net (code "46") (name "Net-(U5-PGTH{slash}~{FLT})") (class "Default")
      (node (ref "R30") (pin "1") (pinfunction "1_1") (pintype "passive"))
      (node (ref "U5") (pin "4") (pinfunction "PGTH/~{FLT}_4") (pintype "passive"))
    )
    (net (code "47") (name "Net-(U5-PG{slash}AUXOFF)") (class "Default")
      (node (ref "R29") (pin "1") (pinfunction "1_1") (pintype "passive"))
      (node (ref "U5") (pin "3") (pinfunction "PG/AUXOFF_3") (pintype "passive"))
    )
    (net (code "48") (name "Net-(U6-EN{slash}UVLO)") (class "Default")
      (node (ref "R37") (pin "1") (pinfunction "1_1") (pintype "passive"))
      (node (ref "R38") (pin "1") (pinfunction "1_1") (pintype "passive"))
      (node (ref "R40") (pin "1") (pinfunction "1_1") (pintype "passive"))
      (node (ref "U6") (pin "1") (pinfunction "EN/UVLO_1") (pintype "passive"))
    )
    (net (code "49") (name "Net-(U6-OVLO{slash}OVCSEL)") (class "Default")
      (node (ref "R33") (pin "1") (pinfunction "1_1") (pintype "passive"))
      (node (ref "R39") (pin "2") (pinfunction "2_2") (pintype "passive"))
      (node (ref "U6") (pin "2") (pinfunction "OVLO/OVCSEL_2") (pintype "passive"))
    )
    (net (code "50") (name "Net-(U6-PGTH{slash}~{FLT})") (class "Default")
      (node (ref "R36") (pin "1") (pinfunction "1_1") (pintype "passive"))
      (node (ref "U6") (pin "4") (pinfunction "PGTH/~{FLT}_4") (pintype "passive"))
    )
    (net (code "51") (name "Net-(U6-PG{slash}AUXOFF)") (class "Default")
      (node (ref "R35") (pin "1") (pinfunction "1_1") (pintype "passive"))
      (node (ref "U6") (pin "3") (pinfunction "PG/AUXOFF_3") (pintype "passive"))
    )
    (net (code "52") (name "Net-(U7-EN{slash}UVLO)") (class "Default")
      (node (ref "R43") (pin "1") (pinfunction "1_1") (pintype "passive"))
      (node (ref "R47") (pin "1") (pinfunction "1_1") (pintype "passive"))
      (node (ref "R48") (pin "1") (pinfunction "1_1") (pintype "passive"))
      (node (ref "U7") (pin "1") (pinfunction "EN/UVLO_1") (pintype "passive"))
    )
    (net (code "53") (name "Net-(U7-OVLO{slash}OVCSEL)") (class "Default")
      (node (ref "R44") (pin "1") (pinfunction "1_1") (pintype "passive"))
      (node (ref "R49") (pin "2") (pinfunction "2_2") (pintype "passive"))
      (node (ref "U7") (pin "2") (pinfunction "OVLO/OVCSEL_2") (pintype "passive"))
    )
    (net (code "54") (name "Net-(U7-PGTH{slash}~{FLT})") (class "Default")
      (node (ref "R46") (pin "1") (pinfunction "1_1") (pintype "passive"))
      (node (ref "U7") (pin "4") (pinfunction "PGTH/~{FLT}_4") (pintype "passive"))
    )
    (net (code "55") (name "Net-(U7-PG{slash}AUXOFF)") (class "Default")
      (node (ref "R45") (pin "1") (pinfunction "1_1") (pintype "passive"))
      (node (ref "U7") (pin "3") (pinfunction "PG/AUXOFF_3") (pintype "passive"))
    )
    (net (code "56") (name "Net-(U8-BOOT)") (class "Default")
      (node (ref "C28") (pin "2") (pinfunction "2_2") (pintype "passive"))
      (node (ref "U8") (pin "1") (pinfunction "BOOT_1") (pintype "power_in"))
    )
    (net (code "57") (name "Net-(U8-PH)") (class "Default")
      (node (ref "C28") (pin "1") (pinfunction "1_1") (pintype "passive"))
      (node (ref "D10") (pin "1") (pinfunction "1_1") (pintype "passive"))
      (node (ref "L2") (pin "1") (pinfunction "1_1") (pintype "passive"))
      (node (ref "U8") (pin "8") (pinfunction "PH_8") (pintype "power_in"))
    )
    (net (code "58") (name "Net-(U8-VSENSE)") (class "Default")
      (node (ref "R51") (pin "1") (pinfunction "1_1") (pintype "passive"))
      (node (ref "R53") (pin "2") (pinfunction "2_2") (pintype "passive"))
      (node (ref "U8") (pin "4") (pinfunction "VSENSE_4") (pintype "input"))
    )
    (net (code "59") (name "Net-(U9-EN)") (class "Default")
      (node (ref "R55") (pin "1") (pinfunction "1_1") (pintype "passive"))
      (node (ref "U9") (pin "3") (pinfunction "EN_3") (pintype "passive"))
    )
    (net (code "60") (name "POW_ONOFF_HD4") (class "Default")
      (node (ref "R31") (pin "2") (pinfunction "2_2") (pintype "passive"))
    )
    (net (code "61") (name "POW_ONOFF_Heater") (class "Default")
      (node (ref "R18") (pin "2") (pinfunction "2_2") (pintype "passive"))
    )
    (net (code "62") (name "POW_ONOFF_IO") (class "Default")
      (node (ref "R15") (pin "2") (pinfunction "2_2") (pintype "passive"))
    )
    (net (code "63") (name "POW_ONOFF_Solenoid") (class "Default")
      (node (ref "R37") (pin "2") (pinfunction "2_2") (pintype "passive"))
    )
    (net (code "64") (name "POW_ONOFF_TEC") (class "Default")
      (node (ref "R47") (pin "2") (pinfunction "2_2") (pintype "passive"))
    )
    (net (code "65") (name "eFUSE_ILIM_5V_HD4") (class "Default")
      (node (ref "R41") (pin "2") (pinfunction "2_2") (pintype "passive"))
      (node (ref "U5") (pin "9") (pinfunction "9_9") (pintype "passive"))
    )
    (net (code "66") (name "eFUSE_ILIM_5V_IO") (class "Default")
      (node (ref "R25") (pin "2") (pinfunction "2_2") (pintype "passive"))
      (node (ref "U3") (pin "9") (pinfunction "9_9") (pintype "passive"))
    )
    (net (code "67") (name "eFUSE_ILIM_5V_TEC") (class "Default")
      (node (ref "R52") (pin "2") (pinfunction "2_2") (pintype "passive"))
      (node (ref "U7") (pin "9") (pinfunction "9_9") (pintype "passive"))
    )
    (net (code "68") (name "eFUSE_ILIM_12V") (class "Default")
      (node (ref "R10") (pin "2") (pinfunction "2_2") (pintype "passive"))
      (node (ref "U2") (pin "9") (pinfunction "9_9") (pintype "passive"))
    )
    (net (code "69") (name "eFUSE_ILIM_12V_Heater") (class "Default")
      (node (ref "R26") (pin "2") (pinfunction "2_2") (pintype "passive"))
      (node (ref "U4") (pin "9") (pinfunction "9_9") (pintype "passive"))
    )
    (net (code "70") (name "eFUSE_ILIM_12V_Solenoid") (class "Default")
      (node (ref "R42") (pin "2") (pinfunction "2_2") (pintype "passive"))
      (node (ref "U6") (pin "9") (pinfunction "9_9") (pintype "passive"))
    )
    (net (code "71") (name "unconnected-(U1-ENA-Pad5)") (class "Default")
      (node (ref "U1") (pin "5") (pinfunction "ENA_5") (pintype "input+no_connect"))
    )
    (net (code "72") (name "unconnected-(U1-NC-Pad2)") (class "Default")
      (node (ref "U1") (pin "2") (pinfunction "NC_2") (pintype "passive"))
    )
    (net (code "73") (name "unconnected-(U1-NC-Pad3)") (class "Default")
      (node (ref "U1") (pin "3") (pinfunction "NC_3") (pintype "passive"))
    )
    (net (code "74") (name "unconnected-(U8-ENA-Pad5)") (class "Default")
      (node (ref "U8") (pin "5") (pinfunction "ENA_5") (pintype "input+no_connect"))
    )
    (net (code "75") (name "unconnected-(U8-NC-Pad2)") (class "Default")
      (node (ref "U8") (pin "2") (pinfunction "NC_2") (pintype "passive"))
    )
    (net (code "76") (name "unconnected-(U8-NC-Pad3)") (class "Default")
      (node (ref "U8") (pin "3") (pinfunction "NC_3") (pintype "passive"))
    )
    (net (code "77") (name "unconnected-(U9-NC-Pad4)") (class "Default")
      (node (ref "U9") (pin "4") (pinfunction "NC_4") (pintype "passive+no_connect"))
    )
  )
)
